# ADXL362_BOB_v01_NO2.net
KiCad netlist of a schematic drawn in EAGLE
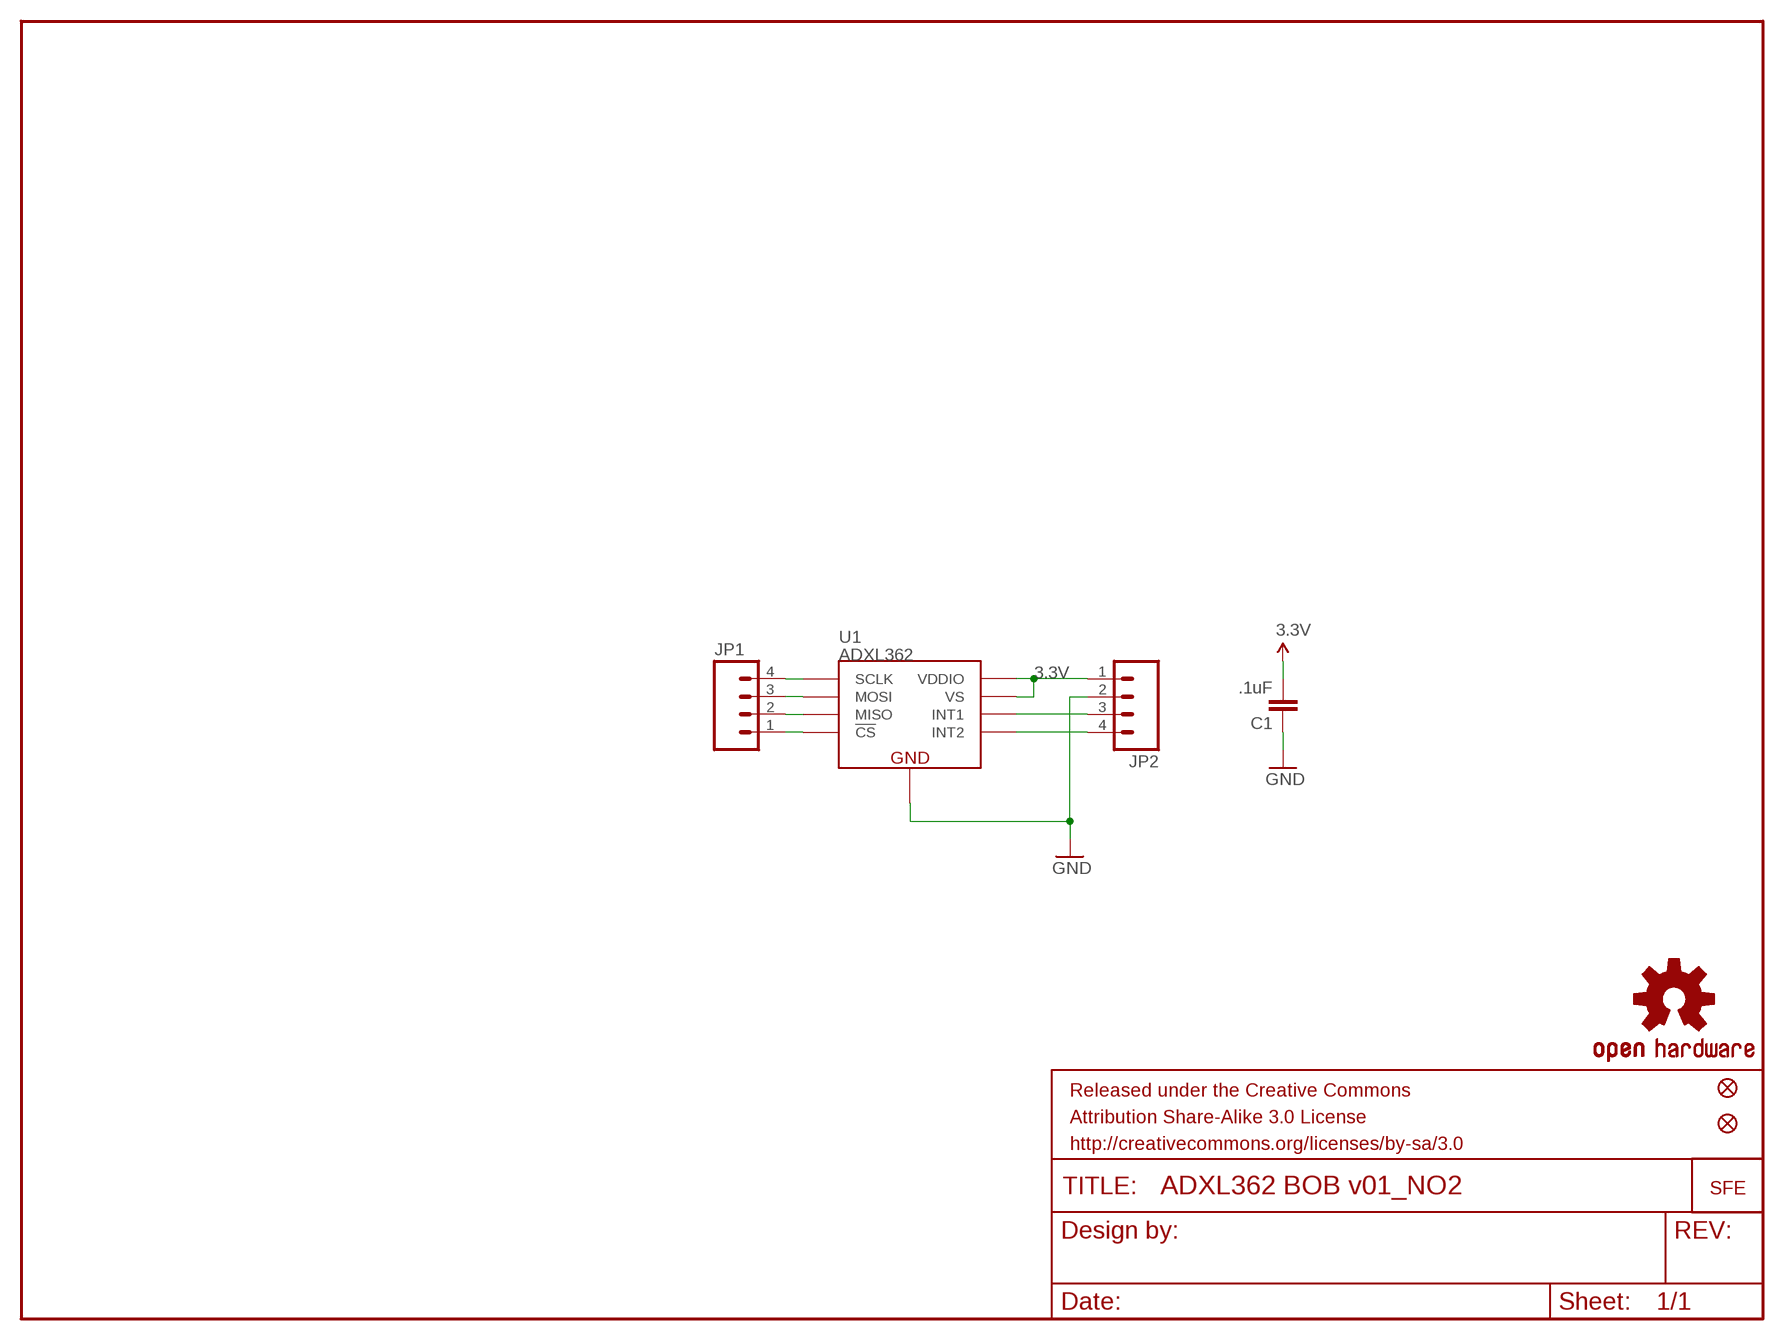
[diagram p0: schematic, sheet 1]

(export (version "E")
  (design (tool "Eeschema 10.0.6"))
  (components
    (comp (ref "C1")
      (value ".1uF")
      (footprint "eagle-import:0402-CAP")
      (libsource (lib "eagle-import") (part "CAP0402-CAP"))
    )
    (comp (ref "FRAME1")
      (value "FRAME-LETTER")
      (footprint "eagle-import:CREATIVE_COMMONS")
      (libsource (lib "eagle-import") (part "FRAME-LETTER"))
    )
    (comp (ref "JP1")
      (value "M04PTH")
      (footprint "eagle-import:1X04")
      (libsource (lib "eagle-import") (part "M04PTH"))
    )
    (comp (ref "JP2")
      (value "M04PTH")
      (footprint "eagle-import:1X04")
      (libsource (lib "eagle-import") (part "M04PTH"))
    )
    (comp (ref "JP3")
      (value "LOGO-SFESK")
      (footprint "eagle-import:SFE-LOGO-FLAME")
      (libsource (lib "eagle-import") (part "LOGO-SFESK"))
    )
    (comp (ref "JP4")
      (value "FIDUCIALUFIDUCIAL")
      (footprint "eagle-import:MICRO-FIDUCIAL")
      (libsource (lib "eagle-import") (part "FIDUCIALUFIDUCIAL"))
    )
    (comp (ref "JP5")
      (value "FIDUCIALUFIDUCIAL")
      (footprint "eagle-import:MICRO-FIDUCIAL")
      (libsource (lib "eagle-import") (part "FIDUCIALUFIDUCIAL"))
    )
    (comp (ref "U$1")
      (value "OSHW-LOGOS")
      (footprint "eagle-import:OSHW-LOGO-S")
      (libsource (lib "eagle-import") (part "OSHW-LOGOS"))
    )
    (comp (ref "U1")
      (value "ADXL362")
      (footprint "eagle-import:ADXL362")
      (libsource (lib "eagle-import") (part "ADXL362"))
    )
  )
  (nets
    (net (code "1") (name "3.3V") (class "Default")
      (node (ref "C1") (pin "2") (pinfunction "2_2") (pintype "passive"))
      (node (ref "JP2") (pin "1") (pinfunction "1_1") (pintype "passive"))
      (node (ref "U1") (pin "P$1") (pinfunction "VDDIO_P$1") (pintype "bidirectional"))
      (node (ref "U1") (pin "P$14") (pinfunction "VS_P$14") (pintype "bidirectional"))
    )
    (net (code "2") (name "GND") (class "Default")
      (node (ref "C1") (pin "1") (pinfunction "1_1") (pintype "passive"))
      (node (ref "JP2") (pin "2") (pinfunction "2_2") (pintype "passive"))
      (node (ref "U1") (pin "P$12") (pinfunction "GND_P$12") (pintype "bidirectional"))
      (node (ref "U1") (pin "P$13") (pinfunction "GND_P$13") (pintype "bidirectional"))
      (node (ref "U1") (pin "P$16") (pinfunction "GND_P$16") (pintype "bidirectional"))
    )
    (net (code "3") (name "Net-(U1-INT1)") (class "Default")
      (node (ref "JP2") (pin "3") (pinfunction "3_3") (pintype "passive"))
      (node (ref "U1") (pin "P$11") (pinfunction "INT1_P$11") (pintype "bidirectional"))
    )
    (net (code "4") (name "Net-(U1-INT2)") (class "Default")
      (node (ref "JP2") (pin "4") (pinfunction "4_4") (pintype "passive"))
      (node (ref "U1") (pin "P$9") (pinfunction "INT2_P$9") (pintype "bidirectional"))
    )
    (net (code "5") (name "Net-(U1-MISO)") (class "Default")
      (node (ref "JP1") (pin "2") (pinfunction "2_2") (pintype "passive"))
      (node (ref "U1") (pin "P$7") (pinfunction "MISO_P$7") (pintype "bidirectional"))
    )
    (net (code "6") (name "Net-(U1-MOSI)") (class "Default")
      (node (ref "JP1") (pin "3") (pinfunction "3_3") (pintype "passive"))
      (node (ref "U1") (pin "P$6") (pinfunction "MOSI_P$6") (pintype "bidirectional"))
    )
    (net (code "7") (name "Net-(U1-SCLK)") (class "Default")
      (node (ref "JP1") (pin "4") (pinfunction "4_4") (pintype "passive"))
      (node (ref "U1") (pin "P$4") (pinfunction "SCLK_P$4") (pintype "bidirectional"))
    )
    (net (code "8") (name "Net-(U1-~{CS})") (class "Default")
      (node (ref "JP1") (pin "1") (pinfunction "1_1") (pintype "passive"))
      (node (ref "U1") (pin "P$8") (pinfunction "~{CS}_P$8") (pintype "bidirectional"))
    )
  )
)
